# smd.net
KiCad netlist of a schematic drawn in EAGLE
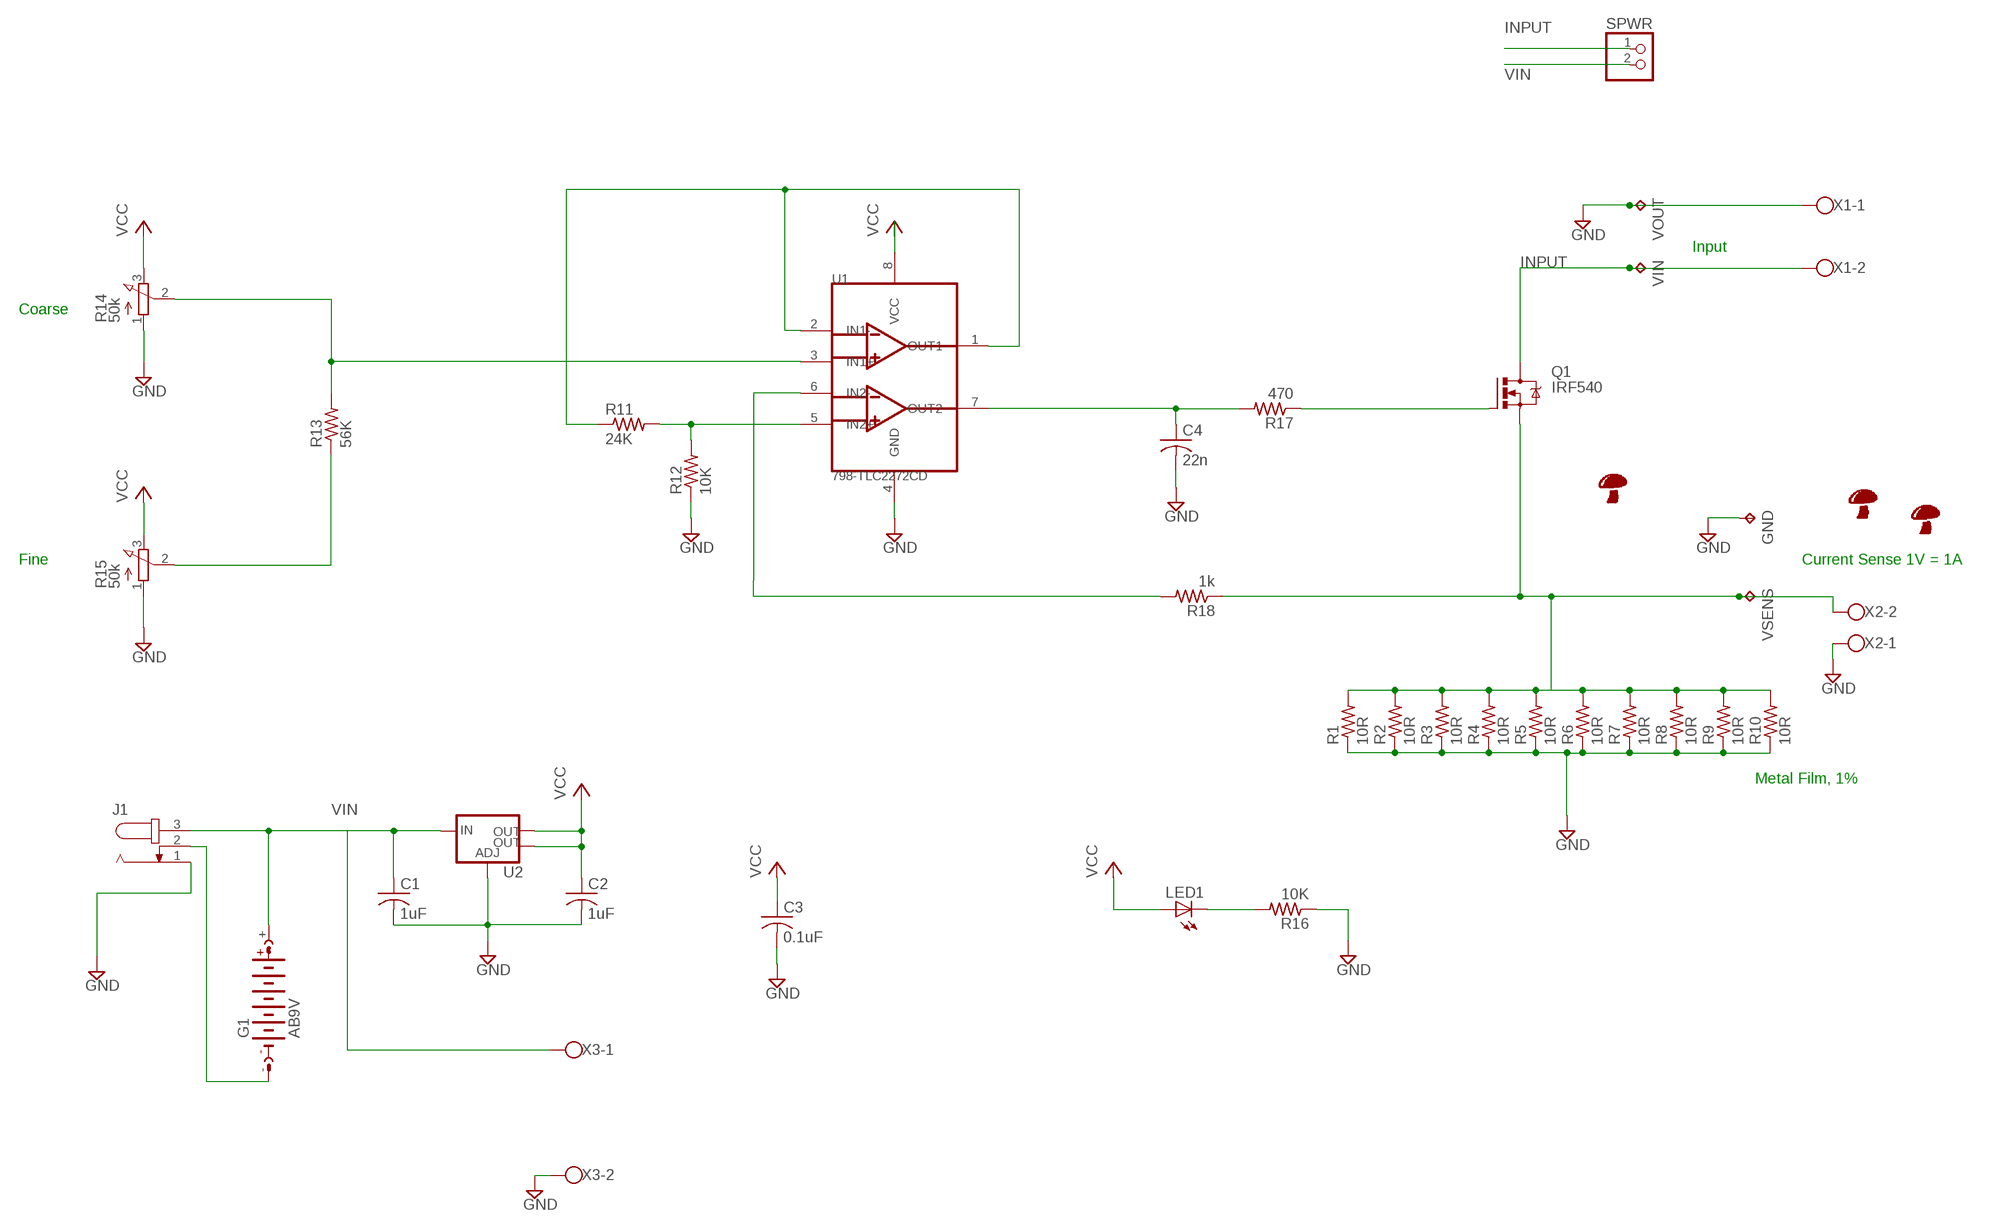
[diagram p0: schematic, sheet 1]

(export (version "E")
  (design (tool "Eeschema 10.0.6"))
  (components
    (comp (ref "C1")
      (value "1uF")
      (footprint "eagle-import:C0805")
      (libsource (lib "eagle-import") (part "C-USC0805"))
    )
    (comp (ref "C2")
      (value "1uF")
      (footprint "eagle-import:C0805")
      (libsource (lib "eagle-import") (part "C-USC0805"))
    )
    (comp (ref "C3")
      (value "0.1uF")
      (footprint "eagle-import:C0805")
      (libsource (lib "eagle-import") (part "C-USC0805"))
    )
    (comp (ref "C4")
      (value "22n")
      (footprint "eagle-import:C0805")
      (libsource (lib "eagle-import") (part "C-USC0805"))
    )
    (comp (ref "G1")
      (value "AB9V")
      (footprint "eagle-import:AB9V")
      (libsource (lib "eagle-import") (part "AB9V"))
    )
    (comp (ref "GND")
      (value "TPPAD1-13Y")
      (footprint "eagle-import:P1-13Y")
      (libsource (lib "eagle-import") (part "TPPAD1-13Y"))
    )
    (comp (ref "J1")
      (value "JACK-PLUG0")
      (footprint "eagle-import:SPC4077")
      (libsource (lib "eagle-import") (part "JACK-PLUG0"))
    )
    (comp (ref "LED1")
      (value "LEDCHIP-LED0805")
      (footprint "eagle-import:CHIP-LED0805")
      (libsource (lib "eagle-import") (part "LEDCHIP-LED0805"))
    )
    (comp (ref "Q1")
      (value "IRF540")
      (footprint "eagle-import:TO220BV")
      (libsource (lib "eagle-import") (part "IRF540"))
    )
    (comp (ref "R1")
      (value "10R")
      (footprint "eagle-import:R2512")
      (libsource (lib "eagle-import") (part "R-US_R2512"))
    )
    (comp (ref "R2")
      (value "10R")
      (footprint "eagle-import:R2512")
      (libsource (lib "eagle-import") (part "R-US_R2512"))
    )
    (comp (ref "R3")
      (value "10R")
      (footprint "eagle-import:R2512")
      (libsource (lib "eagle-import") (part "R-US_R2512"))
    )
    (comp (ref "R4")
      (value "10R")
      (footprint "eagle-import:R2512")
      (libsource (lib "eagle-import") (part "R-US_R2512"))
    )
    (comp (ref "R5")
      (value "10R")
      (footprint "eagle-import:R2512")
      (libsource (lib "eagle-import") (part "R-US_R2512"))
    )
    (comp (ref "R6")
      (value "10R")
      (footprint "eagle-import:R2512")
      (libsource (lib "eagle-import") (part "R-US_R2512"))
    )
    (comp (ref "R7")
      (value "10R")
      (footprint "eagle-import:R2512")
      (libsource (lib "eagle-import") (part "R-US_R2512"))
    )
    (comp (ref "R8")
      (value "10R")
      (footprint "eagle-import:R2512")
      (libsource (lib "eagle-import") (part "R-US_R2512"))
    )
    (comp (ref "R9")
      (value "10R")
      (footprint "eagle-import:R2512")
      (libsource (lib "eagle-import") (part "R-US_R2512"))
    )
    (comp (ref "R10")
      (value "10R")
      (footprint "eagle-import:R2512")
      (libsource (lib "eagle-import") (part "R-US_R2512"))
    )
    (comp (ref "R11")
      (value "24K")
      (footprint "eagle-import:M0805")
      (libsource (lib "eagle-import") (part "R-US_M0805"))
    )
    (comp (ref "R12")
      (value "10K")
      (footprint "eagle-import:M0805")
      (libsource (lib "eagle-import") (part "R-US_M0805"))
    )
    (comp (ref "R13")
      (value "56K")
      (footprint "eagle-import:M0805")
      (libsource (lib "eagle-import") (part "R-US_M0805"))
    )
    (comp (ref "R14")
      (value "50k")
      (footprint "eagle-import:3RP_1610N")
      (libsource (lib "eagle-import") (part "3RP/1610N"))
    )
    (comp (ref "R15")
      (value "50k")
      (footprint "eagle-import:3RP_1610N")
      (libsource (lib "eagle-import") (part "3RP/1610N"))
    )
    (comp (ref "R16")
      (value "10K")
      (footprint "eagle-import:M0805")
      (libsource (lib "eagle-import") (part "R-US_M0805"))
    )
    (comp (ref "R17")
      (value "470")
      (footprint "eagle-import:M0805")
      (libsource (lib "eagle-import") (part "R-US_M0805"))
    )
    (comp (ref "R18")
      (value "1k")
      (footprint "eagle-import:M0805")
      (libsource (lib "eagle-import") (part "R-US_M0805"))
    )
    (comp (ref "SPWR")
      (value "PINHD-1X2")
      (footprint "eagle-import:1X02")
      (libsource (lib "eagle-import") (part "PINHD-1X2"))
    )
    (comp (ref "U$1")
      (value "SHROOM5MM")
      (footprint "eagle-import:SHROOM")
      (libsource (lib "eagle-import") (part "SHROOM5MM"))
    )
    (comp (ref "U$2")
      (value "SHROOM10MM")
      (footprint "eagle-import:SHROOM10MM")
      (libsource (lib "eagle-import") (part "SHROOM10MM"))
    )
    (comp (ref "U$3")
      (value "SHROOMTOPSILK")
      (footprint "eagle-import:SHROOM_TS")
      (libsource (lib "eagle-import") (part "SHROOMTOPSILK"))
    )
    (comp (ref "U1")
      (value "798-TLC2272CD")
      (footprint "eagle-import:ANDREW_B6D66")
      (libsource (lib "eagle-import") (part "798-TLC2272CD"))
    )
    (comp (ref "U2")
      (value "V_REG_LM1117SOT223")
      (footprint "eagle-import:SOT223")
      (libsource (lib "eagle-import") (part "V_REG_LM1117SOT223"))
    )
    (comp (ref "VIN")
      (value "TPPAD1-13Y")
      (footprint "eagle-import:P1-13Y")
      (libsource (lib "eagle-import") (part "TPPAD1-13Y"))
    )
    (comp (ref "VOUT")
      (value "TPPAD1-13Y")
      (footprint "eagle-import:P1-13Y")
      (libsource (lib "eagle-import") (part "TPPAD1-13Y"))
    )
    (comp (ref "VSENS")
      (value "TPPAD1-13Y")
      (footprint "eagle-import:P1-13Y")
      (libsource (lib "eagle-import") (part "TPPAD1-13Y"))
    )
    (comp (ref "X1")
      (value "W237-102")
      (footprint "eagle-import:W237-102")
      (fields (field (name "MPN") "237-102"))
      (libsource (lib "eagle-import") (part "W237-102"))
    )
    (comp (ref "X2")
      (value "W237-102")
      (footprint "eagle-import:W237-102")
      (fields (field (name "MPN") "237-102"))
      (libsource (lib "eagle-import") (part "W237-102"))
    )
    (comp (ref "X3")
      (value "W237-102")
      (footprint "eagle-import:W237-102")
      (fields (field (name "MPN") "237-102"))
      (libsource (lib "eagle-import") (part "W237-102"))
    )
  )
  (nets
    (net (code "1") (name "/INPUT") (class "Default")
      (node (ref "Q1") (pin "D") (pinfunction "D_D") (pintype "passive"))
      (node (ref "SPWR") (pin "1") (pinfunction "1_1") (pintype "passive"))
      (node (ref "VIN") (pin "TP") (pinfunction "TP_TP") (pintype "input"))
      (node (ref "X1") (pin "2") (pinfunction "KL_2") (pintype "passive"))
    )
    (net (code "2") (name "/VIN") (class "Default")
      (node (ref "C1") (pin "1") (pinfunction "1_1") (pintype "passive"))
      (node (ref "G1") (pin "+") (pinfunction "+_+") (pintype "passive"))
      (node (ref "J1") (pin "3") (pinfunction "3_3") (pintype "passive"))
      (node (ref "SPWR") (pin "2") (pinfunction "2_2") (pintype "passive"))
      (node (ref "U2") (pin "3") (pinfunction "IN_3") (pintype "input"))
      (node (ref "X3") (pin "1") (pinfunction "KL_1") (pintype "passive"))
    )
    (net (code "3") (name "GND") (class "Default")
      (node (ref "C1") (pin "2") (pinfunction "2_2") (pintype "passive"))
      (node (ref "C2") (pin "2") (pinfunction "2_2") (pintype "passive"))
      (node (ref "C3") (pin "2") (pinfunction "2_2") (pintype "passive"))
      (node (ref "C4") (pin "2") (pinfunction "2_2") (pintype "passive"))
      (node (ref "GND") (pin "TP") (pinfunction "TP_TP") (pintype "input"))
      (node (ref "J1") (pin "1") (pinfunction "1_1") (pintype "passive"))
      (node (ref "R1") (pin "1") (pinfunction "1_1") (pintype "passive"))
      (node (ref "R10") (pin "1") (pinfunction "1_1") (pintype "passive"))
      (node (ref "R12") (pin "1") (pinfunction "1_1") (pintype "passive"))
      (node (ref "R14") (pin "1") (pinfunction "A_1") (pintype "passive"))
      (node (ref "R15") (pin "1") (pinfunction "A_1") (pintype "passive"))
      (node (ref "R16") (pin "1") (pinfunction "1_1") (pintype "passive"))
      (node (ref "R2") (pin "1") (pinfunction "1_1") (pintype "passive"))
      (node (ref "R3") (pin "1") (pinfunction "1_1") (pintype "passive"))
      (node (ref "R4") (pin "1") (pinfunction "1_1") (pintype "passive"))
      (node (ref "R5") (pin "1") (pinfunction "1_1") (pintype "passive"))
      (node (ref "R6") (pin "1") (pinfunction "1_1") (pintype "passive"))
      (node (ref "R7") (pin "1") (pinfunction "1_1") (pintype "passive"))
      (node (ref "R8") (pin "1") (pinfunction "1_1") (pintype "passive"))
      (node (ref "R9") (pin "1") (pinfunction "1_1") (pintype "passive"))
      (node (ref "U1") (pin "4") (pinfunction "GND_4") (pintype "input"))
      (node (ref "U2") (pin "1") (pinfunction "ADJ_1") (pintype "input"))
      (node (ref "VOUT") (pin "TP") (pinfunction "TP_TP") (pintype "input"))
      (node (ref "X1") (pin "1") (pinfunction "KL_1") (pintype "passive"))
      (node (ref "X2") (pin "1") (pinfunction "KL_1") (pintype "passive"))
      (node (ref "X3") (pin "2") (pinfunction "KL_2") (pintype "passive"))
    )
    (net (code "4") (name "Net-(G1-Pad-)") (class "Default")
      (node (ref "G1") (pin "-") (pinfunction "-_-") (pintype "passive"))
      (node (ref "J1") (pin "2") (pinfunction "2_2") (pintype "passive"))
    )
    (net (code "5") (name "Net-(LED1-PadC)") (class "Default")
      (node (ref "LED1") (pin "C") (pinfunction "C_C") (pintype "passive"))
      (node (ref "R16") (pin "2") (pinfunction "2_2") (pintype "passive"))
    )
    (net (code "6") (name "Net-(Q1-PadG)") (class "Default")
      (node (ref "Q1") (pin "G") (pinfunction "G_G") (pintype "passive"))
      (node (ref "R17") (pin "1") (pinfunction "1_1") (pintype "passive"))
    )
    (net (code "7") (name "Net-(R14-S)") (class "Default")
      (node (ref "R13") (pin "2") (pinfunction "2_2") (pintype "passive"))
      (node (ref "R14") (pin "2") (pinfunction "S_2") (pintype "passive"))
      (node (ref "U1") (pin "3") (pinfunction "IN1+_3") (pintype "input"))
    )
    (net (code "8") (name "Net-(R15-S)") (class "Default")
      (node (ref "R13") (pin "1") (pinfunction "1_1") (pintype "passive"))
      (node (ref "R15") (pin "2") (pinfunction "S_2") (pintype "passive"))
    )
    (net (code "9") (name "Net-(U1-IN1-)") (class "Default")
      (node (ref "R11") (pin "1") (pinfunction "1_1") (pintype "passive"))
      (node (ref "U1") (pin "1") (pinfunction "OUT1_1") (pintype "input"))
      (node (ref "U1") (pin "2") (pinfunction "IN1-_2") (pintype "input"))
    )
    (net (code "10") (name "Net-(U1-IN2+)") (class "Default")
      (node (ref "R11") (pin "2") (pinfunction "2_2") (pintype "passive"))
      (node (ref "R12") (pin "2") (pinfunction "2_2") (pintype "passive"))
      (node (ref "U1") (pin "5") (pinfunction "IN2+_5") (pintype "input"))
    )
    (net (code "11") (name "Net-(U1-IN2-)") (class "Default")
      (node (ref "R18") (pin "2") (pinfunction "2_2") (pintype "passive"))
      (node (ref "U1") (pin "6") (pinfunction "IN2-_6") (pintype "input"))
    )
    (net (code "12") (name "Net-(U1-OUT2)") (class "Default")
      (node (ref "C4") (pin "1") (pinfunction "1_1") (pintype "passive"))
      (node (ref "R17") (pin "2") (pinfunction "2_2") (pintype "passive"))
      (node (ref "U1") (pin "7") (pinfunction "OUT2_7") (pintype "input"))
    )
    (net (code "13") (name "Net-(X2B-KL)") (class "Default")
      (node (ref "Q1") (pin "S") (pinfunction "S_S") (pintype "passive"))
      (node (ref "R1") (pin "2") (pinfunction "2_2") (pintype "passive"))
      (node (ref "R10") (pin "2") (pinfunction "2_2") (pintype "passive"))
      (node (ref "R18") (pin "1") (pinfunction "1_1") (pintype "passive"))
      (node (ref "R2") (pin "2") (pinfunction "2_2") (pintype "passive"))
      (node (ref "R3") (pin "2") (pinfunction "2_2") (pintype "passive"))
      (node (ref "R4") (pin "2") (pinfunction "2_2") (pintype "passive"))
      (node (ref "R5") (pin "2") (pinfunction "2_2") (pintype "passive"))
      (node (ref "R6") (pin "2") (pinfunction "2_2") (pintype "passive"))
      (node (ref "R7") (pin "2") (pinfunction "2_2") (pintype "passive"))
      (node (ref "R8") (pin "2") (pinfunction "2_2") (pintype "passive"))
      (node (ref "R9") (pin "2") (pinfunction "2_2") (pintype "passive"))
      (node (ref "VSENS") (pin "TP") (pinfunction "TP_TP") (pintype "input"))
      (node (ref "X2") (pin "2") (pinfunction "KL_2") (pintype "passive"))
    )
    (net (code "14") (name "VCC") (class "Default")
      (node (ref "C2") (pin "1") (pinfunction "1_1") (pintype "passive"))
      (node (ref "C3") (pin "1") (pinfunction "1_1") (pintype "passive"))
      (node (ref "LED1") (pin "A") (pinfunction "A_A") (pintype "passive"))
      (node (ref "R14") (pin "3") (pinfunction "E_3") (pintype "passive"))
      (node (ref "R15") (pin "3") (pinfunction "E_3") (pintype "passive"))
      (node (ref "U1") (pin "8") (pinfunction "VCC_8") (pintype "input"))
      (node (ref "U2") (pin "2") (pinfunction "OUT_2") (pintype "output"))
      (node (ref "U2") (pin "4") (pinfunction "OUT_4") (pintype "output"))
    )
  )
)
